# h_bridge_v2_1.net
KiCad netlist of a schematic drawn in EAGLE
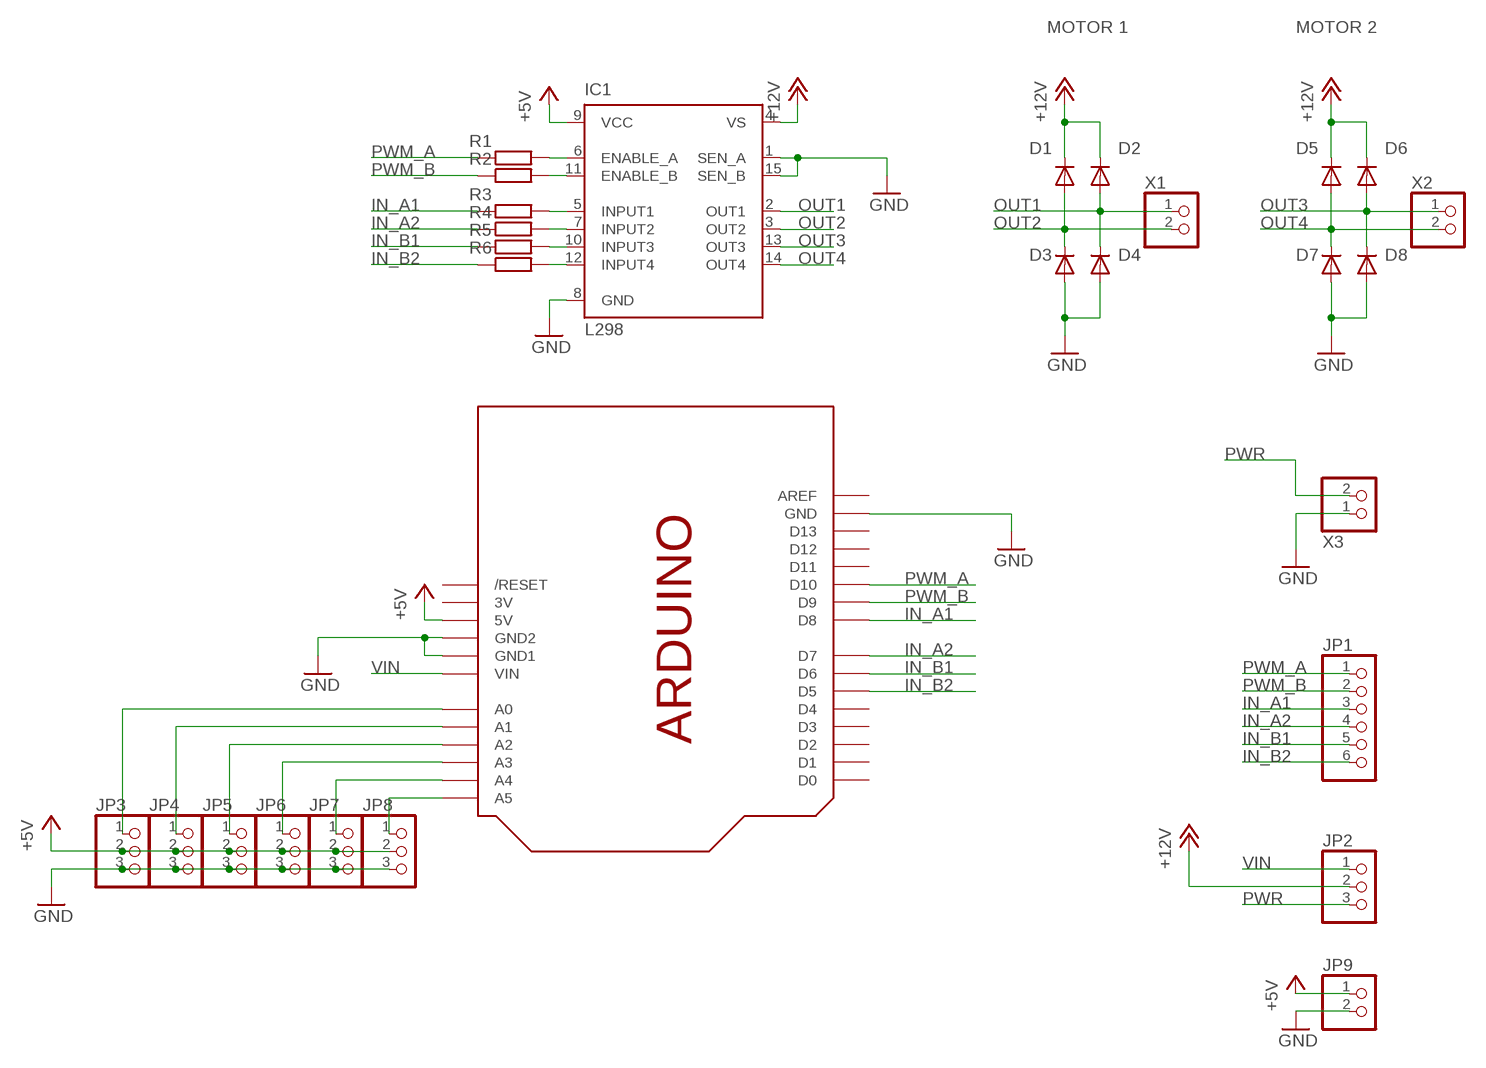
[diagram p0: schematic, sheet 1]

(export (version "E")
  (design (tool "Eeschema 10.0.6"))
  (components
    (comp (ref "D1")
      (value "1N4004A")
      (footprint "eagle-import:DO41-10")
      (libsource (lib "eagle-import") (part "1N4004A"))
    )
    (comp (ref "D2")
      (value "1N4004A")
      (footprint "eagle-import:DO41-10")
      (libsource (lib "eagle-import") (part "1N4004A"))
    )
    (comp (ref "D3")
      (value "1N4004A")
      (footprint "eagle-import:DO41-10")
      (libsource (lib "eagle-import") (part "1N4004A"))
    )
    (comp (ref "D4")
      (value "1N4004A")
      (footprint "eagle-import:DO41-10")
      (libsource (lib "eagle-import") (part "1N4004A"))
    )
    (comp (ref "D5")
      (value "1N4004A")
      (footprint "eagle-import:DO41-10")
      (libsource (lib "eagle-import") (part "1N4004A"))
    )
    (comp (ref "D6")
      (value "1N4004A")
      (footprint "eagle-import:DO41-10")
      (libsource (lib "eagle-import") (part "1N4004A"))
    )
    (comp (ref "D7")
      (value "1N4004A")
      (footprint "eagle-import:DO41-10")
      (libsource (lib "eagle-import") (part "1N4004A"))
    )
    (comp (ref "D8")
      (value "1N4004A")
      (footprint "eagle-import:DO41-10")
      (libsource (lib "eagle-import") (part "1N4004A"))
    )
    (comp (ref "IC1")
      (value "L298")
      (footprint "eagle-import:MULTIWATT-15")
      (fields (field (name "MPN") "L298N"))
      (libsource (lib "eagle-import") (part "L298"))
    )
    (comp (ref "JP1")
      (value "PINHD-1X6")
      (footprint "eagle-import:1X06")
      (libsource (lib "eagle-import") (part "PINHD-1X6"))
    )
    (comp (ref "JP2")
      (value "PINHD-1X3180")
      (footprint "eagle-import:1X03")
      (libsource (lib "eagle-import") (part "PINHD-1X3180"))
    )
    (comp (ref "JP3")
      (value "PINHD-1X3180")
      (footprint "eagle-import:1X03")
      (libsource (lib "eagle-import") (part "PINHD-1X3180"))
    )
    (comp (ref "JP4")
      (value "PINHD-1X3180")
      (footprint "eagle-import:1X03")
      (libsource (lib "eagle-import") (part "PINHD-1X3180"))
    )
    (comp (ref "JP5")
      (value "PINHD-1X3180")
      (footprint "eagle-import:1X03")
      (libsource (lib "eagle-import") (part "PINHD-1X3180"))
    )
    (comp (ref "JP6")
      (value "PINHD-1X3180")
      (footprint "eagle-import:1X03")
      (libsource (lib "eagle-import") (part "PINHD-1X3180"))
    )
    (comp (ref "JP7")
      (value "PINHD-1X3180")
      (footprint "eagle-import:1X03")
      (libsource (lib "eagle-import") (part "PINHD-1X3180"))
    )
    (comp (ref "JP8")
      (value "PINHD-1X3180")
      (footprint "eagle-import:1X03")
      (libsource (lib "eagle-import") (part "PINHD-1X3180"))
    )
    (comp (ref "JP9")
      (value "PINHD-1X2")
      (footprint "eagle-import:1X02")
      (libsource (lib "eagle-import") (part "PINHD-1X2"))
    )
    (comp (ref "R1")
      (value "R-EU_0207/10")
      (footprint "eagle-import:0207_10")
      (libsource (lib "eagle-import") (part "R-EU_0207/10"))
    )
    (comp (ref "R2")
      (value "R-EU_0207/10")
      (footprint "eagle-import:0207_10")
      (libsource (lib "eagle-import") (part "R-EU_0207/10"))
    )
    (comp (ref "R3")
      (value "R-EU_0207/10")
      (footprint "eagle-import:0207_10")
      (libsource (lib "eagle-import") (part "R-EU_0207/10"))
    )
    (comp (ref "R4")
      (value "R-EU_0207/10")
      (footprint "eagle-import:0207_10")
      (libsource (lib "eagle-import") (part "R-EU_0207/10"))
    )
    (comp (ref "R5")
      (value "R-EU_0207/10")
      (footprint "eagle-import:0207_10")
      (libsource (lib "eagle-import") (part "R-EU_0207/10"))
    )
    (comp (ref "R6")
      (value "R-EU_0207/10")
      (footprint "eagle-import:0207_10")
      (libsource (lib "eagle-import") (part "R-EU_0207/10"))
    )
    (comp (ref "U$1")
      (value "ARDUINO-HOLE")
      (footprint "eagle-import:ARDUINO-HOLE")
      (libsource (lib "eagle-import") (part "ARDUINO-HOLE"))
    )
    (comp (ref "X1")
      (value "W237-102")
      (footprint "eagle-import:W237-102")
      (libsource (lib "eagle-import") (part "W237-102"))
    )
    (comp (ref "X2")
      (value "W237-102")
      (footprint "eagle-import:W237-102")
      (libsource (lib "eagle-import") (part "W237-102"))
    )
    (comp (ref "X3")
      (value "W237-102")
      (footprint "eagle-import:W237-102")
      (libsource (lib "eagle-import") (part "W237-102"))
    )
  )
  (nets
    (net (code "1") (name "+5V") (class "Default")
      (node (ref "IC1") (pin "9") (pinfunction "VCC_9") (pintype "power_in"))
      (node (ref "JP3") (pin "2") (pinfunction "2_2") (pintype "passive"))
      (node (ref "JP4") (pin "2") (pinfunction "2_2") (pintype "passive"))
      (node (ref "JP5") (pin "2") (pinfunction "2_2") (pintype "passive"))
      (node (ref "JP6") (pin "2") (pinfunction "2_2") (pintype "passive"))
      (node (ref "JP7") (pin "2") (pinfunction "2_2") (pintype "passive"))
      (node (ref "JP8") (pin "2") (pinfunction "2_2") (pintype "passive"))
      (node (ref "JP9") (pin "1") (pinfunction "1_1") (pintype "passive"))
      (node (ref "U$1") (pin "5V") (pinfunction "5V_5V") (pintype "power_in"))
    )
    (net (code "2") (name "+12V") (class "Default")
      (node (ref "D1") (pin "C") (pinfunction "C_C") (pintype "passive"))
      (node (ref "D2") (pin "C") (pinfunction "C_C") (pintype "passive"))
      (node (ref "D5") (pin "C") (pinfunction "C_C") (pintype "passive"))
      (node (ref "D6") (pin "C") (pinfunction "C_C") (pintype "passive"))
      (node (ref "IC1") (pin "4") (pinfunction "VS_4") (pintype "power_in"))
      (node (ref "JP2") (pin "2") (pinfunction "2_2") (pintype "passive"))
    )
    (net (code "3") (name "/3V") (class "Default")
      (node (ref "U$1") (pin "3V") (pinfunction "3V_3V") (pintype "power_in"))
    )
    (net (code "4") (name "/IN_A1") (class "Default")
      (node (ref "JP1") (pin "3") (pinfunction "3_3") (pintype "passive"))
      (node (ref "R3") (pin "1") (pinfunction "1_1") (pintype "passive"))
      (node (ref "U$1") (pin "D8") (pinfunction "D8_D8") (pintype "bidirectional"))
    )
    (net (code "5") (name "/IN_A2") (class "Default")
      (node (ref "JP1") (pin "4") (pinfunction "4_4") (pintype "passive"))
      (node (ref "R4") (pin "1") (pinfunction "1_1") (pintype "passive"))
      (node (ref "U$1") (pin "D7") (pinfunction "D7_D7") (pintype "bidirectional"))
    )
    (net (code "6") (name "/IN_B1") (class "Default")
      (node (ref "JP1") (pin "5") (pinfunction "5_5") (pintype "passive"))
      (node (ref "R5") (pin "1") (pinfunction "1_1") (pintype "passive"))
      (node (ref "U$1") (pin "D6") (pinfunction "D6_D6") (pintype "bidirectional"))
    )
    (net (code "7") (name "/IN_B2") (class "Default")
      (node (ref "JP1") (pin "6") (pinfunction "6_6") (pintype "passive"))
      (node (ref "R6") (pin "1") (pinfunction "1_1") (pintype "passive"))
      (node (ref "U$1") (pin "D5") (pinfunction "D5_D5") (pintype "bidirectional"))
    )
    (net (code "8") (name "/OUT1") (class "Default")
      (node (ref "D2") (pin "A") (pinfunction "A_A") (pintype "passive"))
      (node (ref "D4") (pin "C") (pinfunction "C_C") (pintype "passive"))
      (node (ref "IC1") (pin "2") (pinfunction "OUT1_2") (pintype "output"))
      (node (ref "X1") (pin "1") (pinfunction "1_1") (pintype "passive"))
    )
    (net (code "9") (name "/OUT2") (class "Default")
      (node (ref "D1") (pin "A") (pinfunction "A_A") (pintype "passive"))
      (node (ref "D3") (pin "C") (pinfunction "C_C") (pintype "passive"))
      (node (ref "IC1") (pin "3") (pinfunction "OUT2_3") (pintype "output"))
      (node (ref "X1") (pin "2") (pinfunction "2_2") (pintype "passive"))
    )
    (net (code "10") (name "/OUT3") (class "Default")
      (node (ref "D6") (pin "A") (pinfunction "A_A") (pintype "passive"))
      (node (ref "D8") (pin "C") (pinfunction "C_C") (pintype "passive"))
      (node (ref "IC1") (pin "13") (pinfunction "OUT3_13") (pintype "output"))
      (node (ref "X2") (pin "1") (pinfunction "1_1") (pintype "passive"))
    )
    (net (code "11") (name "/OUT4") (class "Default")
      (node (ref "D5") (pin "A") (pinfunction "A_A") (pintype "passive"))
      (node (ref "D7") (pin "C") (pinfunction "C_C") (pintype "passive"))
      (node (ref "IC1") (pin "14") (pinfunction "OUT4_14") (pintype "output"))
      (node (ref "X2") (pin "2") (pinfunction "2_2") (pintype "passive"))
    )
    (net (code "12") (name "/PWM_A") (class "Default")
      (node (ref "JP1") (pin "1") (pinfunction "1_1") (pintype "passive"))
      (node (ref "R1") (pin "1") (pinfunction "1_1") (pintype "passive"))
      (node (ref "U$1") (pin "D10") (pinfunction "D10_D10") (pintype "bidirectional"))
    )
    (net (code "13") (name "/PWM_B") (class "Default")
      (node (ref "JP1") (pin "2") (pinfunction "2_2") (pintype "passive"))
      (node (ref "R2") (pin "1") (pinfunction "1_1") (pintype "passive"))
      (node (ref "U$1") (pin "D9") (pinfunction "D9_D9") (pintype "bidirectional"))
    )
    (net (code "14") (name "/PWR") (class "Default")
      (node (ref "JP2") (pin "3") (pinfunction "3_3") (pintype "passive"))
      (node (ref "X3") (pin "2") (pinfunction "2_2") (pintype "passive"))
    )
    (net (code "15") (name "/VIN") (class "Default")
      (node (ref "JP2") (pin "1") (pinfunction "1_1") (pintype "passive"))
      (node (ref "U$1") (pin "VIN") (pinfunction "VIN_VIN") (pintype "power_in"))
    )
    (net (code "16") (name "GND") (class "Default")
      (node (ref "D3") (pin "A") (pinfunction "A_A") (pintype "passive"))
      (node (ref "D4") (pin "A") (pinfunction "A_A") (pintype "passive"))
      (node (ref "D7") (pin "A") (pinfunction "A_A") (pintype "passive"))
      (node (ref "D8") (pin "A") (pinfunction "A_A") (pintype "passive"))
      (node (ref "IC1") (pin "1") (pinfunction "SEN_A_1") (pintype "input"))
      (node (ref "IC1") (pin "15") (pinfunction "SEN_B_15") (pintype "input"))
      (node (ref "IC1") (pin "8") (pinfunction "GND_8") (pintype "power_in"))
      (node (ref "JP3") (pin "3") (pinfunction "3_3") (pintype "passive"))
      (node (ref "JP4") (pin "3") (pinfunction "3_3") (pintype "passive"))
      (node (ref "JP5") (pin "3") (pinfunction "3_3") (pintype "passive"))
      (node (ref "JP6") (pin "3") (pinfunction "3_3") (pintype "passive"))
      (node (ref "JP7") (pin "3") (pinfunction "3_3") (pintype "passive"))
      (node (ref "JP8") (pin "3") (pinfunction "3_3") (pintype "passive"))
      (node (ref "JP9") (pin "2") (pinfunction "2_2") (pintype "passive"))
      (node (ref "U$1") (pin "GND") (pinfunction "GND_GND") (pintype "power_in"))
      (node (ref "U$1") (pin "GND1") (pinfunction "GND1_GND1") (pintype "power_in"))
      (node (ref "U$1") (pin "GND2") (pinfunction "GND2_GND2") (pintype "power_in"))
      (node (ref "X3") (pin "1") (pinfunction "1_1") (pintype "passive"))
    )
    (net (code "17") (name "Net-(IC1-ENABLE_A)") (class "Default")
      (node (ref "IC1") (pin "6") (pinfunction "ENABLE_A_6") (pintype "input"))
      (node (ref "R1") (pin "2") (pinfunction "2_2") (pintype "passive"))
    )
    (net (code "18") (name "Net-(IC1-ENABLE_B)") (class "Default")
      (node (ref "IC1") (pin "11") (pinfunction "ENABLE_B_11") (pintype "input"))
      (node (ref "R2") (pin "2") (pinfunction "2_2") (pintype "passive"))
    )
    (net (code "19") (name "Net-(IC1-INPUT1)") (class "Default")
      (node (ref "IC1") (pin "5") (pinfunction "INPUT1_5") (pintype "input"))
      (node (ref "R3") (pin "2") (pinfunction "2_2") (pintype "passive"))
    )
    (net (code "20") (name "Net-(IC1-INPUT2)") (class "Default")
      (node (ref "IC1") (pin "7") (pinfunction "INPUT2_7") (pintype "input"))
      (node (ref "R4") (pin "2") (pinfunction "2_2") (pintype "passive"))
    )
    (net (code "21") (name "Net-(IC1-INPUT3)") (class "Default")
      (node (ref "IC1") (pin "10") (pinfunction "INPUT3_10") (pintype "input"))
      (node (ref "R5") (pin "2") (pinfunction "2_2") (pintype "passive"))
    )
    (net (code "22") (name "Net-(IC1-INPUT4)") (class "Default")
      (node (ref "IC1") (pin "12") (pinfunction "INPUT4_12") (pintype "input"))
      (node (ref "R6") (pin "2") (pinfunction "2_2") (pintype "passive"))
    )
    (net (code "23") (name "Net-(JP3-Pad1)") (class "Default")
      (node (ref "JP3") (pin "1") (pinfunction "1_1") (pintype "passive"))
      (node (ref "U$1") (pin "A0") (pinfunction "A0_A0") (pintype "bidirectional"))
    )
    (net (code "24") (name "Net-(JP4-Pad1)") (class "Default")
      (node (ref "JP4") (pin "1") (pinfunction "1_1") (pintype "passive"))
      (node (ref "U$1") (pin "A1") (pinfunction "A1_A1") (pintype "bidirectional"))
    )
    (net (code "25") (name "Net-(JP5-Pad1)") (class "Default")
      (node (ref "JP5") (pin "1") (pinfunction "1_1") (pintype "passive"))
      (node (ref "U$1") (pin "A2") (pinfunction "A2_A2") (pintype "bidirectional"))
    )
    (net (code "26") (name "Net-(JP6-Pad1)") (class "Default")
      (node (ref "JP6") (pin "1") (pinfunction "1_1") (pintype "passive"))
      (node (ref "U$1") (pin "A3") (pinfunction "A3_A3") (pintype "bidirectional"))
    )
    (net (code "27") (name "Net-(JP7-Pad1)") (class "Default")
      (node (ref "JP7") (pin "1") (pinfunction "1_1") (pintype "passive"))
      (node (ref "U$1") (pin "A4") (pinfunction "A4_A4") (pintype "bidirectional"))
    )
    (net (code "28") (name "Net-(JP8-Pad1)") (class "Default")
      (node (ref "JP8") (pin "1") (pinfunction "1_1") (pintype "passive"))
      (node (ref "U$1") (pin "A5") (pinfunction "A5_A5") (pintype "bidirectional"))
    )
    (net (code "29") (name "unconnected-(U$1-PadAREF)") (class "Default")
      (node (ref "U$1") (pin "AREF") (pinfunction "AREF_AREF") (pintype "bidirectional"))
    )
    (net (code "30") (name "unconnected-(U$1-PadD0)") (class "Default")
      (node (ref "U$1") (pin "D0") (pinfunction "D0_D0") (pintype "bidirectional"))
    )
    (net (code "31") (name "unconnected-(U$1-PadD1)") (class "Default")
      (node (ref "U$1") (pin "D1") (pinfunction "D1_D1") (pintype "bidirectional"))
    )
    (net (code "32") (name "unconnected-(U$1-PadD2)") (class "Default")
      (node (ref "U$1") (pin "D2") (pinfunction "D2_D2") (pintype "bidirectional"))
    )
    (net (code "33") (name "unconnected-(U$1-PadD3)") (class "Default")
      (node (ref "U$1") (pin "D3") (pinfunction "D3_D3") (pintype "bidirectional"))
    )
    (net (code "34") (name "unconnected-(U$1-PadD4)") (class "Default")
      (node (ref "U$1") (pin "D4") (pinfunction "D4_D4") (pintype "bidirectional"))
    )
    (net (code "35") (name "unconnected-(U$1-PadD11)") (class "Default")
      (node (ref "U$1") (pin "D11") (pinfunction "D11_D11") (pintype "bidirectional"))
    )
    (net (code "36") (name "unconnected-(U$1-PadD12)") (class "Default")
      (node (ref "U$1") (pin "D12") (pinfunction "D12_D12") (pintype "bidirectional"))
    )
    (net (code "37") (name "unconnected-(U$1-PadD13)") (class "Default")
      (node (ref "U$1") (pin "D13") (pinfunction "D13_D13") (pintype "bidirectional"))
    )
    (net (code "38") (name "unconnected-(U$1-{slash}RESET-PadRESET)") (class "Default")
      (node (ref "U$1") (pin "RESET") (pinfunction "/RESET_RESET") (pintype "bidirectional"))
    )
  )
)
